# FastLED_RGB_HSV_Tutorial.net
KiCad netlist of a schematic drawn in EAGLE
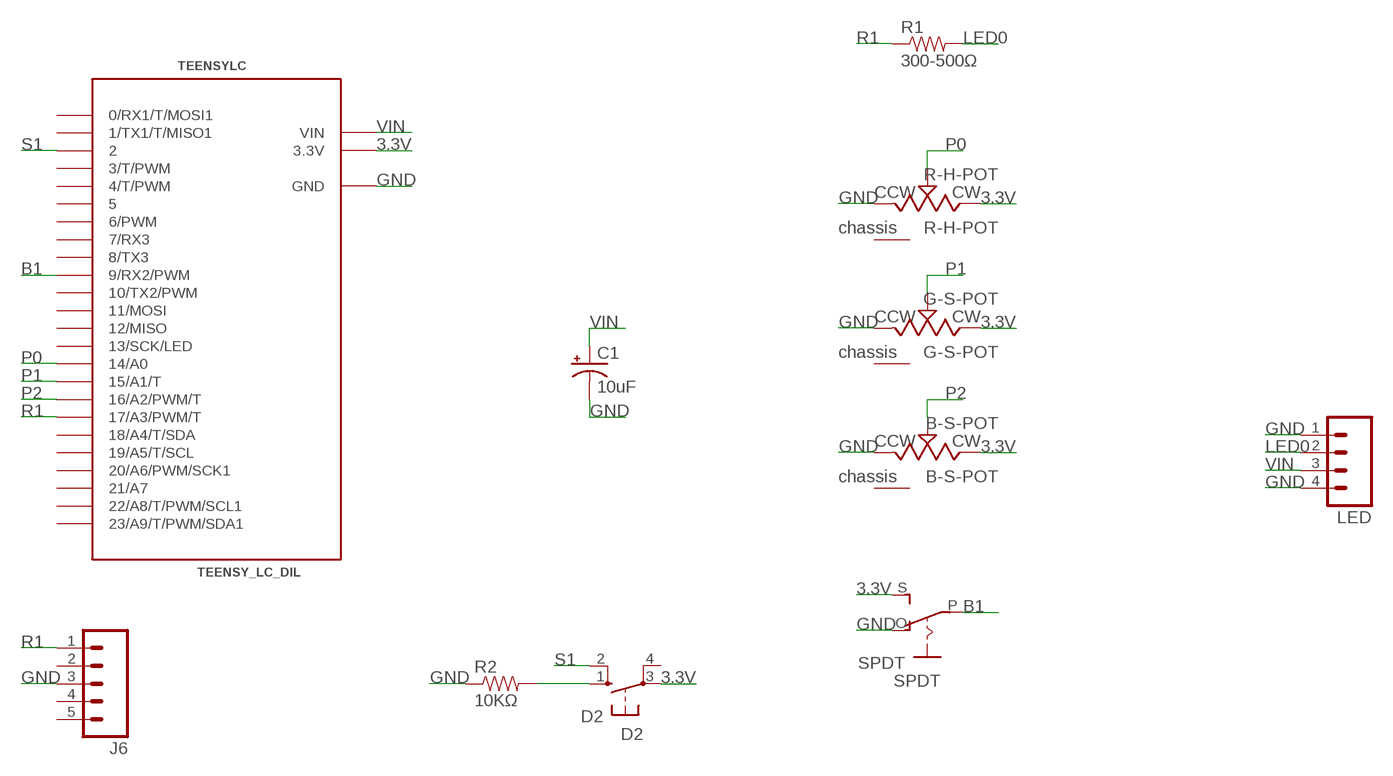
[diagram p0: schematic, sheet 1]

(export (version "E")
  (design (tool "Eeschema 10.0.6"))
  (components
    (comp (ref "B-S-POT")
      (value "B-S-POT")
      (footprint "eagle-import:PTV09A-4")
      (libsource (lib "eagle-import") (part "POTENTIOMETERPTV09A_VERTICAL"))
    )
    (comp (ref "C1")
      (value "10uF")
      (footprint "eagle-import:CPOL-RADIAL-10UF-25V-KIT")
      (libsource (lib "eagle-import") (part "10UF-25V-20%(PTH)KIT"))
    )
    (comp (ref "D2")
      (value "D2")
      (footprint "eagle-import:B3F-10XX")
      (fields (field (name "MPN") "B3F-1000"))
      (libsource (lib "eagle-import") (part "10-XX"))
    )
    (comp (ref "G-S-POT")
      (value "G-S-POT")
      (footprint "eagle-import:PTV09A-4")
      (libsource (lib "eagle-import") (part "POTENTIOMETERPTV09A_VERTICAL"))
    )
    (comp (ref "J6")
      (value "M05PTH")
      (footprint "eagle-import:1X05")
      (libsource (lib "eagle-import") (part "M05PTH"))
    )
    (comp (ref "LED")
      (value "M04PTH")
      (footprint "eagle-import:1X04")
      (libsource (lib "eagle-import") (part "M04PTH"))
    )
    (comp (ref "R-H-POT")
      (value "R-H-POT")
      (footprint "eagle-import:PTV09A-4")
      (libsource (lib "eagle-import") (part "POTENTIOMETERPTV09A_VERTICAL"))
    )
    (comp (ref "R1")
      (value "300-500Ω")
      (footprint "eagle-import:AXIAL-0.1EZ")
      (libsource (lib "eagle-import") (part "RESISTORPTH-1/4W-VERT-KIT"))
    )
    (comp (ref "R2")
      (value "10KΩ")
      (footprint "eagle-import:AXIAL-0.1EZ")
      (libsource (lib "eagle-import") (part "RESISTORPTH-1/4W-VERT-KIT"))
    )
    (comp (ref "SPDT")
      (value "SPDT")
      (footprint "eagle-import:EG1218")
      (libsource (lib "eagle-import") (part "EG1218S"))
    )
    (comp (ref "TEENSYLC")
      (value "TEENSY_LC_DIL")
      (footprint "eagle-import:TEENSY3-DIL")
      (libsource (lib "eagle-import") (part "TEENSY_LC_DIL"))
    )
  )
  (nets
    (net (code "1") (name "/3.3V") (class "Default")
      (node (ref "B-S-POT") (pin "3") (pinfunction "CW_3") (pintype "passive"))
      (node (ref "D2") (pin "3") (pinfunction "P_3") (pintype "passive"))
      (node (ref "G-S-POT") (pin "3") (pinfunction "CW_3") (pintype "passive"))
      (node (ref "R-H-POT") (pin "3") (pinfunction "CW_3") (pintype "passive"))
      (node (ref "SPDT") (pin "S") (pinfunction "S_S") (pintype "passive"))
      (node (ref "TEENSYLC") (pin "3.3V") (pinfunction "3.3V_3.3V") (pintype "power_in"))
    )
    (net (code "2") (name "/B1") (class "Default")
      (node (ref "SPDT") (pin "P") (pinfunction "P_P") (pintype "passive"))
      (node (ref "TEENSYLC") (pin "9") (pinfunction "9/RX2/PWM_9") (pintype "bidirectional"))
    )
    (net (code "3") (name "/GND") (class "Default")
      (node (ref "B-S-POT") (pin "1") (pinfunction "CCW_1") (pintype "passive"))
      (node (ref "C1") (pin "2") (pinfunction "-_2") (pintype "passive"))
      (node (ref "G-S-POT") (pin "1") (pinfunction "CCW_1") (pintype "passive"))
      (node (ref "J6") (pin "3") (pinfunction "3_3") (pintype "passive"))
      (node (ref "LED") (pin "1") (pinfunction "1_1") (pintype "passive"))
      (node (ref "LED") (pin "4") (pinfunction "4_4") (pintype "passive"))
      (node (ref "R-H-POT") (pin "1") (pinfunction "CCW_1") (pintype "passive"))
      (node (ref "R2") (pin "P$1") (pinfunction "1_P$1") (pintype "passive"))
      (node (ref "SPDT") (pin "O") (pinfunction "O_O") (pintype "passive"))
      (node (ref "TEENSYLC") (pin "AGND") (pinfunction "GND_AGND") (pintype "power_in"))
      (node (ref "TEENSYLC") (pin "GND") (pinfunction "GND_GND") (pintype "power_in"))
    )
    (net (code "4") (name "/LED0") (class "Default")
      (node (ref "LED") (pin "2") (pinfunction "2_2") (pintype "passive"))
      (node (ref "R1") (pin "P$2") (pinfunction "2_P$2") (pintype "passive"))
    )
    (net (code "5") (name "/P0") (class "Default")
      (node (ref "R-H-POT") (pin "2") (pinfunction "WIPER_2") (pintype "passive"))
      (node (ref "TEENSYLC") (pin "14/A0") (pinfunction "14/A0_14/A0") (pintype "bidirectional"))
    )
    (net (code "6") (name "/P1") (class "Default")
      (node (ref "G-S-POT") (pin "2") (pinfunction "WIPER_2") (pintype "passive"))
      (node (ref "TEENSYLC") (pin "15/A1") (pinfunction "15/A1/T_15/A1") (pintype "bidirectional"))
    )
    (net (code "7") (name "/P2") (class "Default")
      (node (ref "B-S-POT") (pin "2") (pinfunction "WIPER_2") (pintype "passive"))
      (node (ref "TEENSYLC") (pin "16/A2") (pinfunction "16/A2/PWM/T_16/A2") (pintype "bidirectional"))
    )
    (net (code "8") (name "/R1") (class "Default")
      (node (ref "J6") (pin "1") (pinfunction "1_1") (pintype "passive"))
      (node (ref "R1") (pin "P$1") (pinfunction "1_P$1") (pintype "passive"))
      (node (ref "TEENSYLC") (pin "17/A3") (pinfunction "17/A3/PWM/T_17/A3") (pintype "bidirectional"))
    )
    (net (code "9") (name "/S1") (class "Default")
      (node (ref "D2") (pin "2") (pinfunction "S1_2") (pintype "passive"))
      (node (ref "TEENSYLC") (pin "2") (pinfunction "2_2") (pintype "bidirectional"))
    )
    (net (code "10") (name "/VIN") (class "Default")
      (node (ref "C1") (pin "1") (pinfunction "+_1") (pintype "passive"))
      (node (ref "LED") (pin "3") (pinfunction "3_3") (pintype "passive"))
      (node (ref "TEENSYLC") (pin "VIN") (pinfunction "VIN_VIN") (pintype "power_in"))
    )
    (net (code "11") (name "Net-(D2-S)") (class "Default")
      (node (ref "D2") (pin "1") (pinfunction "S_1") (pintype "passive"))
      (node (ref "R2") (pin "P$2") (pinfunction "2_P$2") (pintype "passive"))
    )
    (net (code "12") (name "unconnected-(B-S-POT-CHASSIS-Pad4)") (class "Default")
      (node (ref "B-S-POT") (pin "4") (pinfunction "CHASSIS_4") (pintype "passive"))
    )
    (net (code "13") (name "unconnected-(D2-P1-Pad4)") (class "Default")
      (node (ref "D2") (pin "4") (pinfunction "P1_4") (pintype "passive"))
    )
    (net (code "14") (name "unconnected-(G-S-POT-CHASSIS-Pad4)") (class "Default")
      (node (ref "G-S-POT") (pin "4") (pinfunction "CHASSIS_4") (pintype "passive"))
    )
    (net (code "15") (name "unconnected-(J6-Pad2)") (class "Default")
      (node (ref "J6") (pin "2") (pinfunction "2_2") (pintype "passive"))
    )
    (net (code "16") (name "unconnected-(J6-Pad4)") (class "Default")
      (node (ref "J6") (pin "4") (pinfunction "4_4") (pintype "passive"))
    )
    (net (code "17") (name "unconnected-(J6-Pad5)") (class "Default")
      (node (ref "J6") (pin "5") (pinfunction "5_5") (pintype "passive"))
    )
    (net (code "18") (name "unconnected-(R-H-POT-CHASSIS-Pad4)") (class "Default")
      (node (ref "R-H-POT") (pin "4") (pinfunction "CHASSIS_4") (pintype "passive"))
    )
    (net (code "19") (name "unconnected-(TEENSYLC-0{slash}RX1{slash}T{slash}MOSI1-Pad0)") (class "Default")
      (node (ref "TEENSYLC") (pin "0") (pinfunction "0/RX1/T/MOSI1_0") (pintype "bidirectional"))
    )
    (net (code "20") (name "unconnected-(TEENSYLC-1{slash}TX1{slash}T{slash}MISO1-Pad1)") (class "Default")
      (node (ref "TEENSYLC") (pin "1") (pinfunction "1/TX1/T/MISO1_1") (pintype "bidirectional"))
    )
    (net (code "21") (name "unconnected-(TEENSYLC-3{slash}T{slash}PWM-Pad3)") (class "Default")
      (node (ref "TEENSYLC") (pin "3") (pinfunction "3/T/PWM_3") (pintype "bidirectional"))
    )
    (net (code "22") (name "unconnected-(TEENSYLC-4{slash}T{slash}PWM-Pad4)") (class "Default")
      (node (ref "TEENSYLC") (pin "4") (pinfunction "4/T/PWM_4") (pintype "bidirectional"))
    )
    (net (code "23") (name "unconnected-(TEENSYLC-6{slash}PWM-Pad6)") (class "Default")
      (node (ref "TEENSYLC") (pin "6") (pinfunction "6/PWM_6") (pintype "bidirectional"))
    )
    (net (code "24") (name "unconnected-(TEENSYLC-7{slash}RX3-Pad7)") (class "Default")
      (node (ref "TEENSYLC") (pin "7") (pinfunction "7/RX3_7") (pintype "bidirectional"))
    )
    (net (code "25") (name "unconnected-(TEENSYLC-8{slash}TX3-Pad8)") (class "Default")
      (node (ref "TEENSYLC") (pin "8") (pinfunction "8/TX3_8") (pintype "bidirectional"))
    )
    (net (code "26") (name "unconnected-(TEENSYLC-10{slash}TX2{slash}PWM-Pad10)") (class "Default")
      (node (ref "TEENSYLC") (pin "10") (pinfunction "10/TX2/PWM_10") (pintype "bidirectional"))
    )
    (net (code "27") (name "unconnected-(TEENSYLC-11{slash}MOSI-Pad11)") (class "Default")
      (node (ref "TEENSYLC") (pin "11") (pinfunction "11/MOSI_11") (pintype "bidirectional"))
    )
    (net (code "28") (name "unconnected-(TEENSYLC-12{slash}MISO-Pad12)") (class "Default")
      (node (ref "TEENSYLC") (pin "12") (pinfunction "12/MISO_12") (pintype "bidirectional"))
    )
    (net (code "29") (name "unconnected-(TEENSYLC-13{slash}SCK{slash}LED-Pad13)") (class "Default")
      (node (ref "TEENSYLC") (pin "13") (pinfunction "13/SCK/LED_13") (pintype "bidirectional"))
    )
    (net (code "30") (name "unconnected-(TEENSYLC-18{slash}A4{slash}T{slash}SDA-Pad18{slash}A4)") (class "Default")
      (node (ref "TEENSYLC") (pin "18/A4") (pinfunction "18/A4/T/SDA_18/A4") (pintype "bidirectional"))
    )
    (net (code "31") (name "unconnected-(TEENSYLC-19{slash}A5{slash}T{slash}SCL-Pad19{slash}A5)") (class "Default")
      (node (ref "TEENSYLC") (pin "19/A5") (pinfunction "19/A5/T/SCL_19/A5") (pintype "bidirectional"))
    )
    (net (code "32") (name "unconnected-(TEENSYLC-20{slash}A6{slash}PWM{slash}SCK1-Pad20{slash}A6)") (class "Default")
      (node (ref "TEENSYLC") (pin "20/A6") (pinfunction "20/A6/PWM/SCK1_20/A6") (pintype "bidirectional"))
    )
    (net (code "33") (name "unconnected-(TEENSYLC-22{slash}A8{slash}T{slash}PWM{slash}SCL1-Pad22{slash}A8)") (class "Default")
      (node (ref "TEENSYLC") (pin "22/A8") (pinfunction "22/A8/T/PWM/SCL1_22/A8") (pintype "bidirectional"))
    )
    (net (code "34") (name "unconnected-(TEENSYLC-23{slash}A9{slash}T{slash}PWM{slash}SDA1-Pad23{slash}A9)") (class "Default")
      (node (ref "TEENSYLC") (pin "23/A9") (pinfunction "23/A9/T/PWM/SDA1_23/A9") (pintype "bidirectional"))
    )
    (net (code "35") (name "unconnected-(TEENSYLC-Pad5)") (class "Default")
      (node (ref "TEENSYLC") (pin "5") (pinfunction "5_5") (pintype "bidirectional"))
    )
    (net (code "36") (name "unconnected-(TEENSYLC-Pad21{slash}A7)") (class "Default")
      (node (ref "TEENSYLC") (pin "21/A7") (pinfunction "21/A7_21/A7") (pintype "bidirectional"))
    )
  )
)
